# ADC.net
KiCad netlist of a schematic drawn in Altium Designer
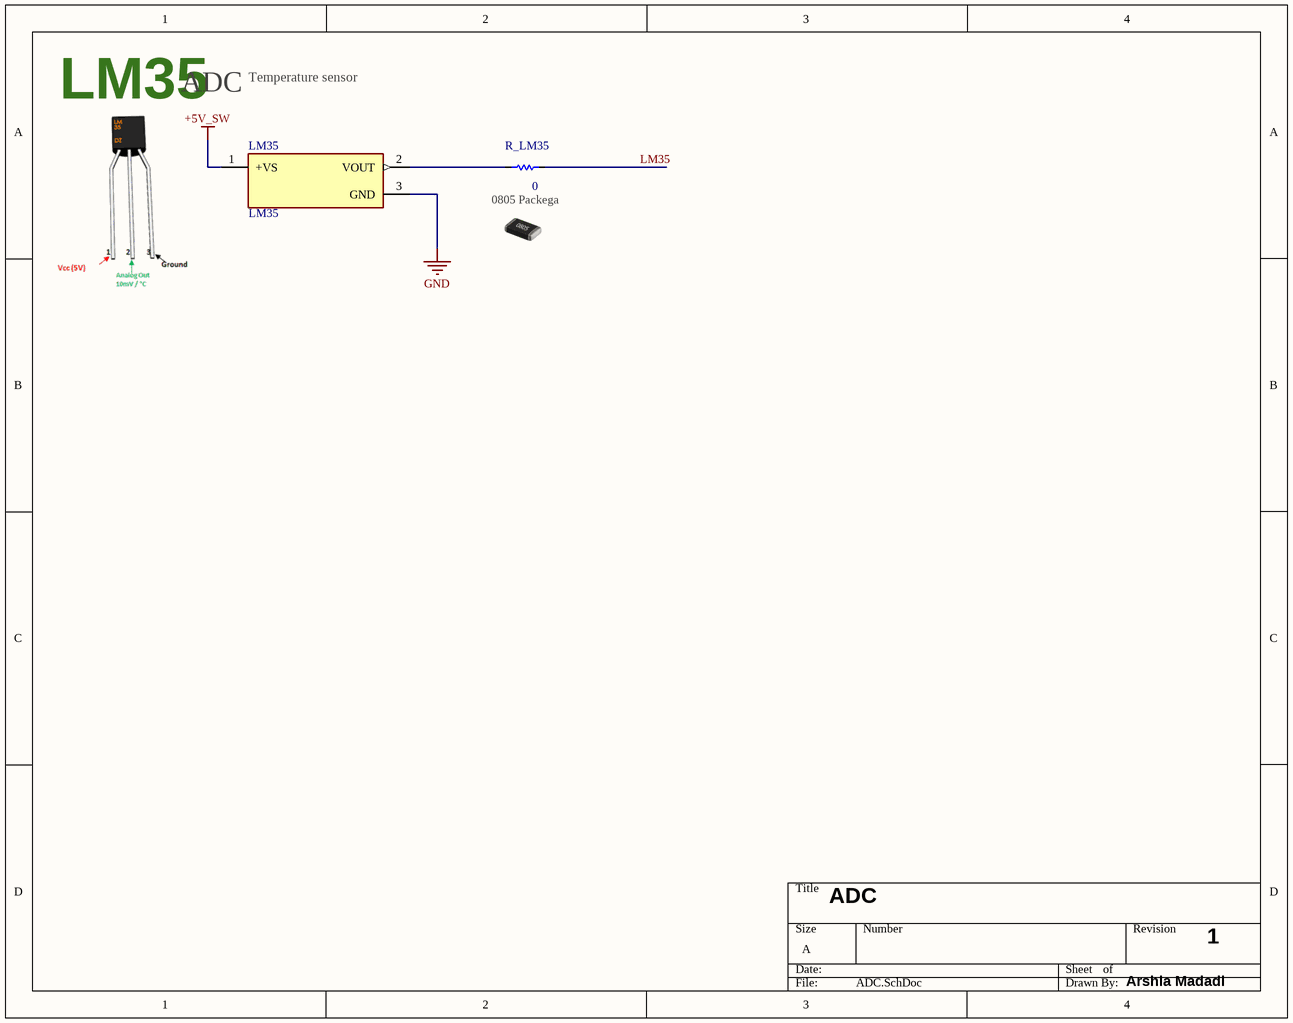
[diagram p0: ADC.SchDoc]

(export (version "E")
  (design (tool "Eeschema 10.0.6"))
  (components
    (comp (ref "LM35")
      (value "LM35")
      (footprint "TO92127P521H735-3")
      (description "Temperature Sensor Analog, Local 0Â°C ~ 100Â°C 10mV/Â°C TO-92-3")
      (fields (field (name "MP") "LM35DZ") (field (name "MF") "Texas Instruments"))
      (libsource (lib "LM35DZ_NOPB") (part "LM35DZ/NOPB"))
    )
    (comp (ref "R_LM35")
      (value "0")
      (footprint "0805")
      (description "Resistor")
      (fields (field (name "PUBLISHER") "Altium Limited"))
      (libsource (lib "Sajad_Altium_Library") (part "Res"))
    )
  )
  (nets
    (net (code "1") (name "+5V_SW") (class "Default")
      (node (ref "LM35") (pin "1") (pinfunction "+VS_1") (pintype "power_in"))
    )
    (net (code "2") (name "/LM35") (class "Default")
      (node (ref "R_LM35") (pin "2") (pinfunction "2_2") (pintype "passive"))
    )
    (net (code "3") (name "GND") (class "Default")
      (node (ref "LM35") (pin "3") (pinfunction "GND_3") (pintype "power_in"))
    )
    (net (code "4") (name "Net-(LM35-VOUT)") (class "Default")
      (node (ref "LM35") (pin "2") (pinfunction "VOUT_2") (pintype "output"))
      (node (ref "R_LM35") (pin "1") (pinfunction "1_1") (pintype "passive"))
    )
  )
)
